# QUTMS-BrakeLight-S00-V00.net
KiCad netlist of a schematic drawn in Altium Designer
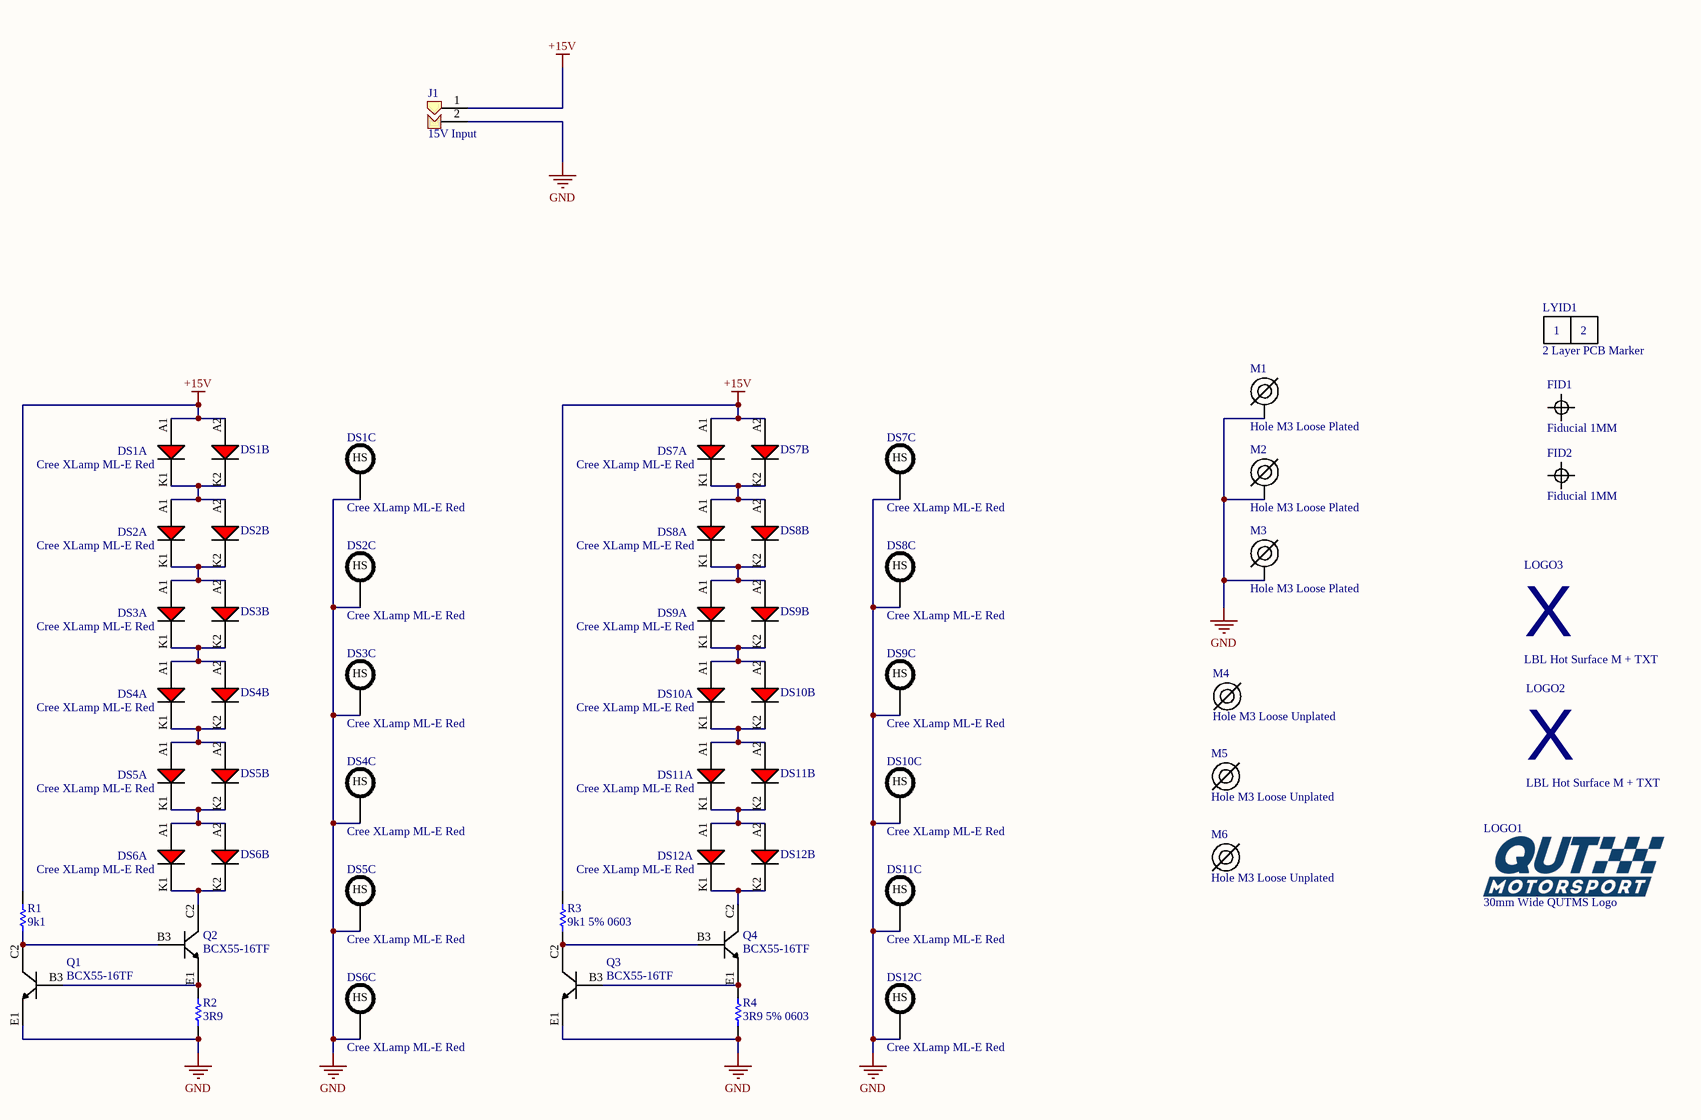
[diagram p0: QUTMS-BrakeLight-S00-V00.SchDoc]

(export (version "E")
  (design (tool "Eeschema 10.0.6"))
  (components
    (comp (ref "DS1")
      (value "Cree XLamp ML-E Red")
      (footprint "CREE XLAMP ML-E")
      (libsource (lib "QUTMS_LEDLibrary") (part "Cree XLamp ML-E Red"))
    )
    (comp (ref "DS2")
      (value "Cree XLamp ML-E Red")
      (footprint "CREE XLAMP ML-E")
      (libsource (lib "QUTMS_LEDLibrary") (part "Cree XLamp ML-E Red"))
    )
    (comp (ref "DS3")
      (value "Cree XLamp ML-E Red")
      (footprint "CREE XLAMP ML-E")
      (libsource (lib "QUTMS_LEDLibrary") (part "Cree XLamp ML-E Red"))
    )
    (comp (ref "DS4")
      (value "Cree XLamp ML-E Red")
      (footprint "CREE XLAMP ML-E")
      (libsource (lib "QUTMS_LEDLibrary") (part "Cree XLamp ML-E Red"))
    )
    (comp (ref "DS5")
      (value "Cree XLamp ML-E Red")
      (footprint "CREE XLAMP ML-E")
      (libsource (lib "QUTMS_LEDLibrary") (part "Cree XLamp ML-E Red"))
    )
    (comp (ref "DS6")
      (value "Cree XLamp ML-E Red")
      (footprint "CREE XLAMP ML-E")
      (libsource (lib "QUTMS_LEDLibrary") (part "Cree XLamp ML-E Red"))
    )
    (comp (ref "DS7")
      (value "Cree XLamp ML-E Red")
      (footprint "CREE XLAMP ML-E")
      (libsource (lib "QUTMS_LEDLibrary") (part "Cree XLamp ML-E Red"))
    )
    (comp (ref "DS8")
      (value "Cree XLamp ML-E Red")
      (footprint "CREE XLAMP ML-E")
      (libsource (lib "QUTMS_LEDLibrary") (part "Cree XLamp ML-E Red"))
    )
    (comp (ref "DS9")
      (value "Cree XLamp ML-E Red")
      (footprint "CREE XLAMP ML-E")
      (libsource (lib "QUTMS_LEDLibrary") (part "Cree XLamp ML-E Red"))
    )
    (comp (ref "DS10")
      (value "Cree XLamp ML-E Red")
      (footprint "CREE XLAMP ML-E")
      (libsource (lib "QUTMS_LEDLibrary") (part "Cree XLamp ML-E Red"))
    )
    (comp (ref "DS11")
      (value "Cree XLamp ML-E Red")
      (footprint "CREE XLAMP ML-E")
      (libsource (lib "QUTMS_LEDLibrary") (part "Cree XLamp ML-E Red"))
    )
    (comp (ref "DS12")
      (value "Cree XLamp ML-E Red")
      (footprint "CREE XLAMP ML-E")
      (libsource (lib "QUTMS_LEDLibrary") (part "Cree XLamp ML-E Red"))
    )
    (comp (ref "FID1")
      (value "Fiducial 1MM")
      (footprint "FIDUCIAL 1MM")
      (libsource (lib "QUTMS_PCBLibrary") (part "Fiducial 1MM"))
    )
    (comp (ref "FID2")
      (value "Fiducial 1MM")
      (footprint "FIDUCIAL 1MM")
      (libsource (lib "QUTMS_PCBLibrary") (part "Fiducial 1MM"))
    )
    (comp (ref "J1")
      (value "15V Input")
      (footprint "Jumper_2Way_Large_Solder_Pad")
      (description "Jumper 2Way Side Large Solderable Pad")
      (libsource (lib "QUTMS_JumperLibrary") (part "Jumper 2Way Side Large Solder Pad"))
    )
    (comp (ref "LOGO1")
      (value "30mm Wide QUTMS Logo")
      (footprint "QUTMS LOGO 30MM")
      (libsource (lib "QUTMS_PCBLibrary") (part "QUTMS Logo 30mm"))
    )
    (comp (ref "LOGO2")
      (value "LBL Hot Surface M + TXT")
      (footprint "LBL HOT MEDIUM TXT")
      (libsource (lib "QUTMS_PCBLibrary") (part "LBL Hot Surface M + TXT"))
    )
    (comp (ref "LOGO3")
      (value "LBL Hot Surface M + TXT")
      (footprint "LBL HOT MEDIUM TXT")
      (libsource (lib "QUTMS_PCBLibrary") (part "LBL Hot Surface M + TXT"))
    )
    (comp (ref "LYID1")
      (value "2 Layer PCB Marker")
      (footprint "LAYER IDENT 2")
      (description "2 Layer Identification PCB Marker")
      (libsource (lib "QUTMS_PCBLibrary") (part "Layer Identification 2"))
    )
    (comp (ref "M1")
      (value "Hole M3 Loose Plated")
      (footprint "M3.5 PLATED")
      (description "M3.5 Hole, Plated")
      (libsource (lib "QUTMS_PCBLibrary") (part "Hole M3 Loose Plated"))
    )
    (comp (ref "M2")
      (value "Hole M3 Loose Plated")
      (footprint "M3.5 PLATED")
      (description "M3.5 Hole, Plated")
      (libsource (lib "QUTMS_PCBLibrary") (part "Hole M3 Loose Plated"))
    )
    (comp (ref "M3")
      (value "Hole M3 Loose Plated")
      (footprint "M3.5 PLATED")
      (description "M3.5 Hole, Plated")
      (libsource (lib "QUTMS_PCBLibrary") (part "Hole M3 Loose Plated"))
    )
    (comp (ref "M4")
      (value "Hole M3 Loose Unplated")
      (footprint "M3.5 UNPLATED")
      (description "M3.5 Hole, No Plating")
      (libsource (lib "QUTMS_PCBLibrary") (part "Hole M3 Loose Unplated"))
    )
    (comp (ref "M5")
      (value "Hole M3 Loose Unplated")
      (footprint "M3.5 UNPLATED")
      (description "M3.5 Hole, No Plating")
      (libsource (lib "QUTMS_PCBLibrary") (part "Hole M3 Loose Unplated"))
    )
    (comp (ref "M6")
      (value "Hole M3 Loose Unplated")
      (footprint "M3.5 UNPLATED")
      (description "M3.5 Hole, No Plating")
      (libsource (lib "QUTMS_PCBLibrary") (part "Hole M3 Loose Unplated"))
    )
    (comp (ref "Q1")
      (value "BCX55-16TF")
      (footprint "SOT89")
      (description "BCX55-16TF -  Bipolar (BJT) Single Transistor, NPN, 60 V, 155 MHz, 500 mW, 1 A, 100 hFE")
      (libsource (lib "QUTMS_TransistorLibrary") (part "BJT NPN Transistor"))
    )
    (comp (ref "Q2")
      (value "BCX55-16TF")
      (footprint "SOT89")
      (description "BCX55-16TF -  Bipolar (BJT) Single Transistor, NPN, 60 V, 155 MHz, 500 mW, 1 A, 100 hFE")
      (libsource (lib "QUTMS_TransistorLibrary") (part "BJT NPN Transistor"))
    )
    (comp (ref "Q3")
      (value "BCX55-16TF")
      (footprint "SOT89")
      (description "BCX55-16TF -  Bipolar (BJT) Single Transistor, NPN, 60 V, 155 MHz, 500 mW, 1 A, 100 hFE")
      (libsource (lib "QUTMS_TransistorLibrary") (part "BJT NPN Transistor"))
    )
    (comp (ref "Q4")
      (value "BCX55-16TF")
      (footprint "SOT89")
      (description "BCX55-16TF -  Bipolar (BJT) Single Transistor, NPN, 60 V, 155 MHz, 500 mW, 1 A, 100 hFE")
      (libsource (lib "QUTMS_TransistorLibrary") (part "BJT NPN Transistor"))
    )
    (comp (ref "R1")
      (value "9k1")
      (footprint "Res_ThinFilm_0603")
      (description "Resistor, SMD, 9k1, 0.1W, 5%, 0603")
      (libsource (lib "StandardResistors") (part "9k1 5% 0603"))
    )
    (comp (ref "R2")
      (value "3R9")
      (footprint "Res_ThinFilm_0603")
      (description "Resistor, SMD, 3R9, 0.1W, 5%, 0603")
      (libsource (lib "StandardResistors") (part "3R9 5% 0603"))
    )
    (comp (ref "R3")
      (value "9k1 5% 0603")
      (footprint "Res_ThinFilm_0603")
      (description "Resistor, SMD, 9k1, 0.1W, 5%, 0603")
      (libsource (lib "StandardResistors") (part "9k1 5% 0603"))
    )
    (comp (ref "R4")
      (value "3R9 5% 0603")
      (footprint "Res_ThinFilm_0603")
      (description "Resistor, SMD, 3R9, 0.1W, 5%, 0603")
      (libsource (lib "StandardResistors") (part "3R9 5% 0603"))
    )
  )
  (nets
    (net (code "1") (name "+15V") (class "Default")
      (node (ref "DS1") (pin "A1") (pinfunction "A_A1") (pintype "passive"))
      (node (ref "DS1") (pin "A2") (pinfunction "A_A2") (pintype "passive"))
      (node (ref "DS7") (pin "A1") (pinfunction "A_A1") (pintype "passive"))
      (node (ref "DS7") (pin "A2") (pinfunction "A_A2") (pintype "passive"))
      (node (ref "J1") (pin "1") (pinfunction "1_1") (pintype "passive"))
      (node (ref "R1") (pin "1") (pinfunction "1_1") (pintype "passive"))
      (node (ref "R3") (pin "1") (pinfunction "1_1") (pintype "passive"))
    )
    (net (code "2") (name "GND") (class "Default")
      (node (ref "DS1") (pin "HS") (pinfunction "HS_HS") (pintype "passive"))
      (node (ref "DS10") (pin "HS") (pinfunction "HS_HS") (pintype "passive"))
      (node (ref "DS11") (pin "HS") (pinfunction "HS_HS") (pintype "passive"))
      (node (ref "DS12") (pin "HS") (pinfunction "HS_HS") (pintype "passive"))
      (node (ref "DS2") (pin "HS") (pinfunction "HS_HS") (pintype "passive"))
      (node (ref "DS3") (pin "HS") (pinfunction "HS_HS") (pintype "passive"))
      (node (ref "DS4") (pin "HS") (pinfunction "HS_HS") (pintype "passive"))
      (node (ref "DS5") (pin "HS") (pinfunction "HS_HS") (pintype "passive"))
      (node (ref "DS6") (pin "HS") (pinfunction "HS_HS") (pintype "passive"))
      (node (ref "DS7") (pin "HS") (pinfunction "HS_HS") (pintype "passive"))
      (node (ref "DS8") (pin "HS") (pinfunction "HS_HS") (pintype "passive"))
      (node (ref "DS9") (pin "HS") (pinfunction "HS_HS") (pintype "passive"))
      (node (ref "J1") (pin "2") (pinfunction "2_2") (pintype "passive"))
      (node (ref "M1") (pin "1") (pinfunction "1_1") (pintype "passive"))
      (node (ref "M2") (pin "1") (pinfunction "1_1") (pintype "passive"))
      (node (ref "M3") (pin "1") (pinfunction "1_1") (pintype "passive"))
      (node (ref "Q1") (pin "E1") (pinfunction "E1_E1") (pintype "passive"))
      (node (ref "Q3") (pin "E1") (pinfunction "E1_E1") (pintype "passive"))
      (node (ref "R2") (pin "1") (pinfunction "1_1") (pintype "passive"))
      (node (ref "R4") (pin "1") (pinfunction "1_1") (pintype "passive"))
    )
    (net (code "3") (name "Net-(DS1A-K)") (class "Default")
      (node (ref "DS1") (pin "K1") (pinfunction "K_K1") (pintype "passive"))
      (node (ref "DS1") (pin "K2") (pinfunction "K_K2") (pintype "passive"))
      (node (ref "DS2") (pin "A1") (pinfunction "A_A1") (pintype "passive"))
      (node (ref "DS2") (pin "A2") (pinfunction "A_A2") (pintype "passive"))
    )
    (net (code "4") (name "Net-(DS2A-K)") (class "Default")
      (node (ref "DS2") (pin "K1") (pinfunction "K_K1") (pintype "passive"))
      (node (ref "DS2") (pin "K2") (pinfunction "K_K2") (pintype "passive"))
      (node (ref "DS3") (pin "A1") (pinfunction "A_A1") (pintype "passive"))
      (node (ref "DS3") (pin "A2") (pinfunction "A_A2") (pintype "passive"))
    )
    (net (code "5") (name "Net-(DS3A-K)") (class "Default")
      (node (ref "DS3") (pin "K1") (pinfunction "K_K1") (pintype "passive"))
      (node (ref "DS3") (pin "K2") (pinfunction "K_K2") (pintype "passive"))
      (node (ref "DS4") (pin "A1") (pinfunction "A_A1") (pintype "passive"))
      (node (ref "DS4") (pin "A2") (pinfunction "A_A2") (pintype "passive"))
    )
    (net (code "6") (name "Net-(DS4A-K)") (class "Default")
      (node (ref "DS4") (pin "K1") (pinfunction "K_K1") (pintype "passive"))
      (node (ref "DS4") (pin "K2") (pinfunction "K_K2") (pintype "passive"))
      (node (ref "DS5") (pin "A1") (pinfunction "A_A1") (pintype "passive"))
      (node (ref "DS5") (pin "A2") (pinfunction "A_A2") (pintype "passive"))
    )
    (net (code "7") (name "Net-(DS5A-K)") (class "Default")
      (node (ref "DS5") (pin "K1") (pinfunction "K_K1") (pintype "passive"))
      (node (ref "DS5") (pin "K2") (pinfunction "K_K2") (pintype "passive"))
      (node (ref "DS6") (pin "A1") (pinfunction "A_A1") (pintype "passive"))
      (node (ref "DS6") (pin "A2") (pinfunction "A_A2") (pintype "passive"))
    )
    (net (code "8") (name "Net-(DS6A-K)") (class "Default")
      (node (ref "DS6") (pin "K1") (pinfunction "K_K1") (pintype "passive"))
      (node (ref "DS6") (pin "K2") (pinfunction "K_K2") (pintype "passive"))
      (node (ref "Q2") (pin "C2") (pinfunction "C2_C2") (pintype "passive"))
    )
    (net (code "9") (name "Net-(DS7A-K)") (class "Default")
      (node (ref "DS7") (pin "K1") (pinfunction "K_K1") (pintype "passive"))
      (node (ref "DS7") (pin "K2") (pinfunction "K_K2") (pintype "passive"))
      (node (ref "DS8") (pin "A1") (pinfunction "A_A1") (pintype "passive"))
      (node (ref "DS8") (pin "A2") (pinfunction "A_A2") (pintype "passive"))
    )
    (net (code "10") (name "Net-(DS8A-K)") (class "Default")
      (node (ref "DS8") (pin "K1") (pinfunction "K_K1") (pintype "passive"))
      (node (ref "DS8") (pin "K2") (pinfunction "K_K2") (pintype "passive"))
      (node (ref "DS9") (pin "A1") (pinfunction "A_A1") (pintype "passive"))
      (node (ref "DS9") (pin "A2") (pinfunction "A_A2") (pintype "passive"))
    )
    (net (code "11") (name "Net-(DS10A-A)") (class "Default")
      (node (ref "DS10") (pin "A1") (pinfunction "A_A1") (pintype "passive"))
      (node (ref "DS10") (pin "A2") (pinfunction "A_A2") (pintype "passive"))
      (node (ref "DS9") (pin "K1") (pinfunction "K_K1") (pintype "passive"))
      (node (ref "DS9") (pin "K2") (pinfunction "K_K2") (pintype "passive"))
    )
    (net (code "12") (name "Net-(DS10A-K)") (class "Default")
      (node (ref "DS10") (pin "K1") (pinfunction "K_K1") (pintype "passive"))
      (node (ref "DS10") (pin "K2") (pinfunction "K_K2") (pintype "passive"))
      (node (ref "DS11") (pin "A1") (pinfunction "A_A1") (pintype "passive"))
      (node (ref "DS11") (pin "A2") (pinfunction "A_A2") (pintype "passive"))
    )
    (net (code "13") (name "Net-(DS11A-K)") (class "Default")
      (node (ref "DS11") (pin "K1") (pinfunction "K_K1") (pintype "passive"))
      (node (ref "DS11") (pin "K2") (pinfunction "K_K2") (pintype "passive"))
      (node (ref "DS12") (pin "A1") (pinfunction "A_A1") (pintype "passive"))
      (node (ref "DS12") (pin "A2") (pinfunction "A_A2") (pintype "passive"))
    )
    (net (code "14") (name "Net-(DS12A-K)") (class "Default")
      (node (ref "DS12") (pin "K1") (pinfunction "K_K1") (pintype "passive"))
      (node (ref "DS12") (pin "K2") (pinfunction "K_K2") (pintype "passive"))
      (node (ref "Q4") (pin "C2") (pinfunction "C2_C2") (pintype "passive"))
    )
    (net (code "15") (name "Net-(Q1-PadB3)") (class "Default")
      (node (ref "Q1") (pin "B3") (pinfunction "B3_B3") (pintype "passive"))
      (node (ref "Q2") (pin "E1") (pinfunction "E1_E1") (pintype "passive"))
      (node (ref "R2") (pin "2") (pinfunction "2_2") (pintype "passive"))
    )
    (net (code "16") (name "Net-(Q1-PadC2)") (class "Default")
      (node (ref "Q1") (pin "C2") (pinfunction "C2_C2") (pintype "passive"))
      (node (ref "Q2") (pin "B3") (pinfunction "B3_B3") (pintype "passive"))
      (node (ref "R1") (pin "2") (pinfunction "2_2") (pintype "passive"))
    )
    (net (code "17") (name "Net-(Q3-PadB3)") (class "Default")
      (node (ref "Q3") (pin "B3") (pinfunction "B3_B3") (pintype "passive"))
      (node (ref "Q4") (pin "E1") (pinfunction "E1_E1") (pintype "passive"))
      (node (ref "R4") (pin "2") (pinfunction "2_2") (pintype "passive"))
    )
    (net (code "18") (name "Net-(Q3-PadC2)") (class "Default")
      (node (ref "Q3") (pin "C2") (pinfunction "C2_C2") (pintype "passive"))
      (node (ref "Q4") (pin "B3") (pinfunction "B3_B3") (pintype "passive"))
      (node (ref "R3") (pin "2") (pinfunction "2_2") (pintype "passive"))
    )
  )
)
